# 1_V2.net
KiCad netlist of a schematic drawn in Altium Designer
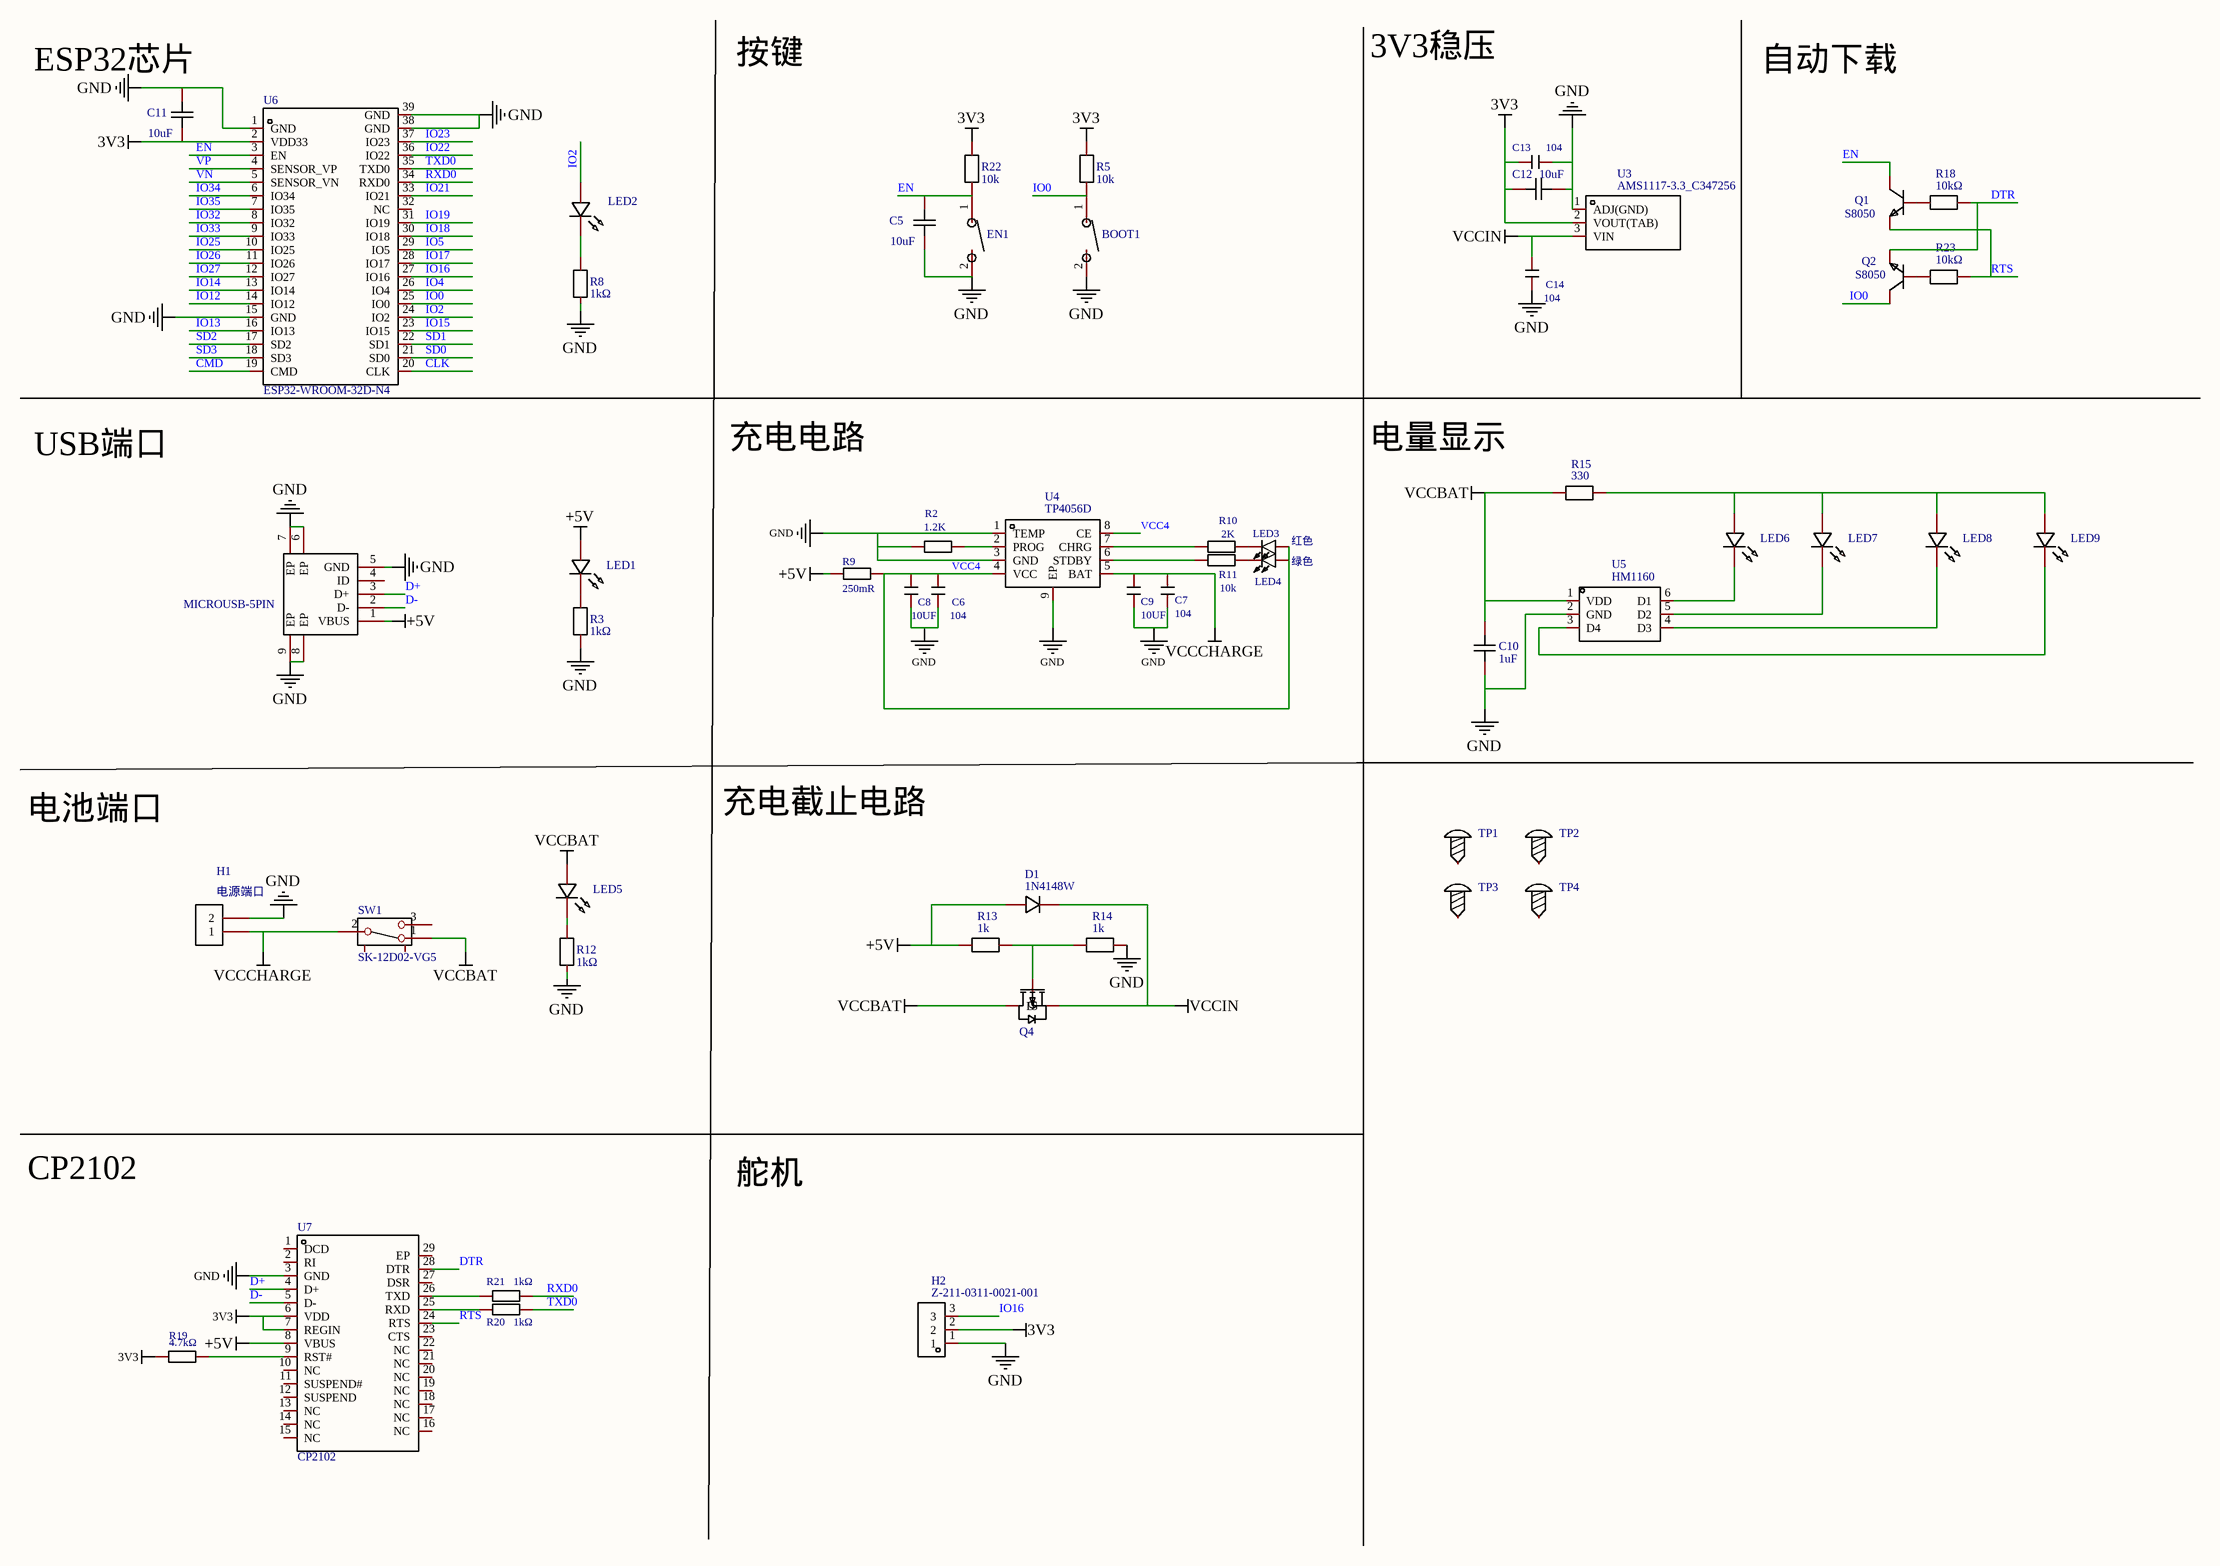
[diagram p0: 1_V2.schdoc]

(export (version "E")
  (design (tool "Eeschema 10.0.6"))
  (components
    (comp (ref "BOOT1")
      (value "TSA343G00-250J2")
      (fields (field (name "MANUFACTURER") "BRIGHT(博瑞泰)"))
      (libsource (lib "altium-import") (part "root_3_TSA343G00-250J2_"))
    )
    (comp (ref "C5")
      (value "10uF")
      (fields (field (name "NAME") "10uF"))
      (libsource (lib "altium-import") (part "root_1_10uF_"))
    )
    (comp (ref "C6")
      (value "104")
      (fields (field (name "NAME") "104") (field (name "版权归属") "源创客"))
      (libsource (lib "altium-import") (part "root_1_104_"))
    )
    (comp (ref "C7")
      (value "104")
      (fields (field (name "NAME") "104") (field (name "版权归属") "源创客"))
      (libsource (lib "altium-import") (part "root_1_104_"))
    )
    (comp (ref "C8")
      (value "10UF")
      (fields (field (name "NAME") "10UF") (field (name "版权归属") "源创客"))
      (libsource (lib "altium-import") (part "root_1_10UF_"))
    )
    (comp (ref "C9")
      (value "10UF")
      (fields (field (name "NAME") "10UF") (field (name "版权归属") "源创客"))
      (libsource (lib "altium-import") (part "root_1_10UF_"))
    )
    (comp (ref "C10")
      (value "1uF")
      (fields (field (name "NAME") "1uF"))
      (libsource (lib "altium-import") (part "root_1_1uF_"))
    )
    (comp (ref "C11")
      (value "10uF")
      (fields (field (name "NAME") "10uF"))
      (libsource (lib "altium-import") (part "root_1_10uF_"))
    )
    (comp (ref "C12")
      (value "10uF")
      (fields (field (name "NAME") "10uF"))
      (libsource (lib "altium-import") (part "root_0_10uF_"))
    )
    (comp (ref "C13")
      (value "104")
      (fields (field (name "NAME") "104") (field (name "版权归属") "源创客"))
      (libsource (lib "altium-import") (part "root_2_104_"))
    )
    (comp (ref "C14")
      (value "104")
      (fields (field (name "NAME") "104") (field (name "版权归属") "源创客"))
      (libsource (lib "altium-import") (part "root_1_104_"))
    )
    (comp (ref "D1")
      (value "1N4148W")
      (fields (field (name "NAME") "1N4148W") (field (name "MANUFACTURER") "Tak Cheong"))
      (libsource (lib "altium-import") (part "root_0_1N4148W_"))
    )
    (comp (ref "EN1")
      (value "TSA343G00-250J2")
      (fields (field (name "MANUFACTURER") "BRIGHT(博瑞泰)"))
      (libsource (lib "altium-import") (part "root_3_TSA343G00-250J2_"))
    )
    (comp (ref "H1")
      (value "电源端口")
      (fields
        (field (name "NAME") "电源端口")
        (field (name "MANUFACTURER") "TE Connectivity(美国泰科)")
        (field (name "MANUFACTURER PART") "3-644456-2")
      )
      (libsource (lib "altium-import") (part "root_2_电源端口_"))
    )
    (comp (ref "H2")
      (value "Z-211-0311-0021-001")
      (fields (field (name "NAME") "Z-211-0311-0021-001") (field (name "MANUFACTURER") "Nextron(正凌)"))
      (libsource (lib "altium-import") (part "root_2_Z-211-0311-0021-001_"))
    )
    (comp (ref "LED1")
      (value "LED-0603_R")
      (fields
        (field (name "MANUFACTURER") "EVERLIGHT(台湾亿光)")
        (field (name "MANUFACTURER PART") "19-217/R6C-AL1M2VY/3T")
      )
      (libsource (lib "altium-import") (part "root_3_LED-0603_R_"))
    )
    (comp (ref "LED2")
      (value "VLMTG1401-GS08")
      (description "照明颜色:-;色温 - CCT（K）:-;主波长/色坐标:-;正向电压（Vf）:-;")
      (fields (field (name "MANUFACTURER") "VISHAY(威世)"))
      (libsource (lib "altium-import") (part "root_3_VLMTG1401-GS08_"))
    )
    (comp (ref "LED3")
      (value "红色")
      (fields (field (name "NAME") "红色") (field (name "版权归属") "源创客"))
      (libsource (lib "altium-import") (part "root_3_红色_"))
    )
    (comp (ref "LED4")
      (value "绿色")
      (fields (field (name "NAME") "绿色") (field (name "版权归属") "源创客"))
      (libsource (lib "altium-import") (part "root_3_绿色_"))
    )
    (comp (ref "LED5")
      (value "LED-0603_R")
      (fields
        (field (name "MANUFACTURER") "EVERLIGHT(台湾亿光)")
        (field (name "MANUFACTURER PART") "19-217/R6C-AL1M2VY/3T")
      )
      (libsource (lib "altium-import") (part "root_3_LED-0603_R_"))
    )
    (comp (ref "LED6")
      (value "LED-0603_R")
      (fields
        (field (name "MANUFACTURER") "EVERLIGHT(台湾亿光)")
        (field (name "MANUFACTURER PART") "19-217/R6C-AL1M2VY/3T")
      )
      (libsource (lib "altium-import") (part "root_3_LED-0603_R_"))
    )
    (comp (ref "LED7")
      (value "LED-0603_R")
      (fields
        (field (name "MANUFACTURER") "EVERLIGHT(台湾亿光)")
        (field (name "MANUFACTURER PART") "19-217/R6C-AL1M2VY/3T")
      )
      (libsource (lib "altium-import") (part "root_3_LED-0603_R_"))
    )
    (comp (ref "LED8")
      (value "LED-0603_R")
      (fields
        (field (name "MANUFACTURER") "EVERLIGHT(台湾亿光)")
        (field (name "MANUFACTURER PART") "19-217/R6C-AL1M2VY/3T")
      )
      (libsource (lib "altium-import") (part "root_3_LED-0603_R_"))
    )
    (comp (ref "LED9")
      (value "LED-0603_R")
      (fields
        (field (name "MANUFACTURER") "EVERLIGHT(台湾亿光)")
        (field (name "MANUFACTURER PART") "19-217/R6C-AL1M2VY/3T")
      )
      (libsource (lib "altium-import") (part "root_3_LED-0603_R_"))
    )
    (comp (ref "NO1")
      (value "MICROUSB-5PIN")
      (fields (field (name "NAME") "MICROUSB-5PIN") (field (name "MANUFACTURER PART") "MicroUSB-5PIN"))
      (libsource (lib "altium-import") (part "root_2_MICROUSB-5PIN_"))
    )
    (comp (ref "Q1")
      (value "S8050")
      (fields (field (name "NAME") "S8050") (field (name "MANUFACTURER") "WPMtek(维攀微)"))
      (libsource (lib "altium-import") (part "root_0_S8050_"))
    )
    (comp (ref "Q2")
      (value "S8050")
      (fields (field (name "NAME") "S8050") (field (name "MANUFACTURER") "WPMtek(维攀微)"))
      (libsource (lib "altium-import") (part "root_2_S8050_"))
    )
    (comp (ref "Q4")
      (value "AO3401A_P")
      (libsource (lib "altium-import") (part "root_3_mirrored_AO3401A_P_"))
    )
    (comp (ref "R2")
      (value "1.2K")
      (fields (field (name "NAME") "1.2K") (field (name "版权归属") "源创客"))
      (libsource (lib "altium-import") (part "root_0_1K_"))
    )
    (comp (ref "R3")
      (value "1kΩ")
      (fields
        (field (name "NAME") "1kΩ")
        (field (name "MANUFACTURER") "PANASONIC(松下)")
        (field (name "MANUFACTURER PART") "ERA3VEB1001V")
        (field (name "TOLERANCE") "±0.1%")
      )
      (libsource (lib "altium-import") (part "root_3_ERA3VEB1001V_"))
    )
    (comp (ref "R5")
      (value "10k")
      (fields (field (name "NAME") "10k"))
      (libsource (lib "altium-import") (part "root_1_10k_"))
    )
    (comp (ref "R8")
      (value "1kΩ")
      (fields
        (field (name "NAME") "1kΩ")
        (field (name "MANUFACTURER") "PANASONIC(松下)")
        (field (name "MANUFACTURER PART") "ERA3VEB1001V")
        (field (name "TOLERANCE") "±0.1%")
      )
      (libsource (lib "altium-import") (part "root_3_ERA3VEB1001V_"))
    )
    (comp (ref "R9")
      (value "250mR")
      (fields (field (name "NAME") "250mR") (field (name "版权归属") "源创客"))
      (libsource (lib "altium-import") (part "root_0_250mR_"))
    )
    (comp (ref "R10")
      (value "2K")
      (fields (field (name "NAME") "2K") (field (name "版权归属") "源创客"))
      (libsource (lib "altium-import") (part "root_0_2K_"))
    )
    (comp (ref "R11")
      (value "10k")
      (fields (field (name "NAME") "10k") (field (name "版权归属") "源创客"))
      (libsource (lib "altium-import") (part "root_0_10k_"))
    )
    (comp (ref "R12")
      (value "1kΩ")
      (fields
        (field (name "NAME") "1kΩ")
        (field (name "MANUFACTURER") "PANASONIC(松下)")
        (field (name "MANUFACTURER PART") "ERA3VEB1001V")
        (field (name "TOLERANCE") "±0.1%")
      )
      (libsource (lib "altium-import") (part "root_3_ERA3VEB1001V_"))
    )
    (comp (ref "R13")
      (value "1k")
      (fields (field (name "NAME") "1k"))
      (libsource (lib "altium-import") (part "root_0_1k_"))
    )
    (comp (ref "R14")
      (value "1k")
      (fields (field (name "NAME") "1k"))
      (libsource (lib "altium-import") (part "root_0_1k_"))
    )
    (comp (ref "R15")
      (value "330")
      (fields (field (name "NAME") "330"))
      (libsource (lib "altium-import") (part "root_0_330_"))
    )
    (comp (ref "R18")
      (value "10kΩ")
      (description "电阻类型:厚膜电阻;阻值:10kΩ;精度:±0.1%;功率:200mW;温度系数:±50ppm/℃;最大工作电压:200V;工作温度范围:-55℃~+155℃;")
      (fields
        (field (name "NAME") "10kΩ")
        (field (name "MANUFACTURER") "PANASONIC(松下)")
        (field (name "MANUFACTURER PART") "ERJPB3B1002V")
      )
      (libsource (lib "altium-import") (part "root_0_ERJPB3B1002V_"))
    )
    (comp (ref "R19")
      (value "4.7kΩ")
      (description "电阻类型:薄膜电阻;阻值:4.7kΩ;精度:±0.1%;功率:125mW;")
      (fields
        (field (name "NAME") "4.7kΩ")
        (field (name "MANUFACTURER") "VISHAY(威世)")
        (field (name "MANUFACTURER PART") "TNPW06034K70BEEA")
        (field (name "版权归属") "源创客")
      )
      (libsource (lib "altium-import") (part "root_0_TNPW06034K70BEEA_"))
    )
    (comp (ref "R20")
      (value "1kΩ")
      (fields
        (field (name "NAME") "1kΩ")
        (field (name "MANUFACTURER") "PANASONIC(松下)")
        (field (name "MANUFACTURER PART") "ERA3VEB1001V")
        (field (name "TOLERANCE") "±0.1%")
        (field (name "版权归属") "源创客")
      )
      (libsource (lib "altium-import") (part "root_0_ERA3VEB1001V_"))
    )
    (comp (ref "R21")
      (value "1kΩ")
      (fields
        (field (name "NAME") "1kΩ")
        (field (name "MANUFACTURER") "PANASONIC(松下)")
        (field (name "MANUFACTURER PART") "ERA3VEB1001V")
        (field (name "TOLERANCE") "±0.1%")
        (field (name "版权归属") "源创客")
      )
      (libsource (lib "altium-import") (part "root_0_ERA3VEB1001V_"))
    )
    (comp (ref "R22")
      (value "10k")
      (fields (field (name "NAME") "10k"))
      (libsource (lib "altium-import") (part "root_1_10k_"))
    )
    (comp (ref "R23")
      (value "10kΩ")
      (description "电阻类型:厚膜电阻;阻值:10kΩ;精度:±0.1%;功率:200mW;温度系数:±50ppm/℃;最大工作电压:200V;工作温度范围:-55℃~+155℃;")
      (fields
        (field (name "NAME") "10kΩ")
        (field (name "MANUFACTURER") "PANASONIC(松下)")
        (field (name "MANUFACTURER PART") "ERJPB3B1002V")
      )
      (libsource (lib "altium-import") (part "root_0_ERJPB3B1002V_"))
    )
    (comp (ref "SW1")
      (value "SK-12D02-VG5")
      (fields (field (name "NAME") "SK-12D02-VG5") (field (name "MANUFACTURER") "韩国韩荣"))
      (libsource (lib "altium-import") (part "root_0_SK-12D02-VG5_C136722_"))
    )
    (comp (ref "TP1") (value "M2螺丝") (libsource (lib "altium-import") (part "root_0_M2螺丝_")))
    (comp (ref "TP2") (value "M2螺丝") (libsource (lib "altium-import") (part "root_0_M2螺丝_")))
    (comp (ref "TP3") (value "M2螺丝") (libsource (lib "altium-import") (part "root_0_M2螺丝_")))
    (comp (ref "TP4") (value "M2螺丝") (libsource (lib "altium-import") (part "root_0_M2螺丝_")))
    (comp (ref "U3")
      (value "AMS1117-3.3_C347256")
      (fields
        (field (name "NAME") "AMS1117-3.3_C347256")
        (field (name "MANUFACTURER") "Youtai Semiconductor Co., Ltd.")
        (field (name "MANUFACTURER PART") "AMS1117-3.3")
      )
      (libsource (lib "altium-import") (part "root_0_AMS1117-3.3_C347256_"))
    )
    (comp (ref "U4")
      (value "TP4056D")
      (fields (field (name "NAME") "TP4056D") (field (name "MANUFACTURER") "拓微集成"))
      (libsource (lib "altium-import") (part "root_0_TP4056D_"))
    )
    (comp (ref "U5")
      (value "HM1160")
      (fields
        (field (name "NAME") "HM1160")
        (field (name "MANUFACTURER") "Shenzhen Chip Hope Micro-Electronics")
        (field (name "MANUFACTURER PART") "LP3772-1")
      )
      (libsource (lib "altium-import") (part "root_0_HM1160_"))
    )
    (comp (ref "U6")
      (value "ESP32-WROOM-32D-N4")
      (description "ESP32-WROOM-32D 集成 ESP32-D0WD，功能强大，用途广泛，可以用于低功耗传感器网络和要求极高的任务，例如语音编码、音频流和 MP3 解码等。")
      (fields (field (name "NAME") "ESP32-WROOM-32D-N4") (field (name "MANUFACTURER") "ESPRESSIF(乐鑫)"))
      (libsource (lib "altium-import") (part "root_0_ESP32-WROOM-32D-N4_C473012_"))
    )
    (comp (ref "U7")
      (value "CP2102")
      (fields (field (name "NAME") "CP2102"))
      (libsource (lib "altium-import") (part "root_0_CP2102_"))
    )
  )
  (nets
    (net (code "1") (name "+5V") (class "Default")
      (node (ref "D1") (pin "2") (pinfunction "2_2") (pintype "passive"))
      (node (ref "LED1") (pin "1") (pinfunction "1_1") (pintype "passive"))
      (node (ref "NO1") (pin "1") (pinfunction "VBUS_1") (pintype "passive"))
      (node (ref "R13") (pin "1") (pinfunction "1_1") (pintype "passive"))
      (node (ref "R9") (pin "1") (pinfunction "1_1") (pintype "passive"))
      (node (ref "U7") (pin "8") (pinfunction "VBUS_8") (pintype "passive"))
    )
    (net (code "2") (name "/CLK") (class "Default")
      (node (ref "U6") (pin "20") (pinfunction "CLK_20") (pintype "passive"))
    )
    (net (code "3") (name "/CMD") (class "Default")
      (node (ref "U6") (pin "19") (pinfunction "CMD_19") (pintype "passive"))
    )
    (net (code "4") (name "/D+") (class "Default")
      (node (ref "NO1") (pin "3") (pinfunction "D+_3") (pintype "passive"))
      (node (ref "U7") (pin "4") (pinfunction "D+_4") (pintype "passive"))
    )
    (net (code "5") (name "/D-") (class "Default")
      (node (ref "NO1") (pin "2") (pinfunction "D-_2") (pintype "passive"))
      (node (ref "U7") (pin "5") (pinfunction "D-_5") (pintype "passive"))
    )
    (net (code "6") (name "/DTR") (class "Default")
      (node (ref "Q2") (pin "2") (pinfunction "E_2") (pintype "passive"))
      (node (ref "R18") (pin "2") (pinfunction "2_2") (pintype "passive"))
      (node (ref "U7") (pin "28") (pinfunction "DTR_28") (pintype "passive"))
    )
    (net (code "7") (name "/EN") (class "Default")
      (node (ref "C5") (pin "2") (pinfunction "2_2") (pintype "passive"))
      (node (ref "EN1") (pin "1") (pinfunction "1_1") (pintype "passive"))
      (node (ref "Q1") (pin "3") (pinfunction "C_3") (pintype "passive"))
      (node (ref "R22") (pin "1") (pinfunction "1_1") (pintype "passive"))
      (node (ref "U6") (pin "3") (pinfunction "EN_3") (pintype "passive"))
    )
    (net (code "8") (name "/IO0") (class "Default")
      (node (ref "BOOT1") (pin "1") (pinfunction "1_1") (pintype "passive"))
      (node (ref "Q2") (pin "3") (pinfunction "C_3") (pintype "passive"))
      (node (ref "R5") (pin "1") (pinfunction "1_1") (pintype "passive"))
      (node (ref "U6") (pin "25") (pinfunction "IO0_25") (pintype "passive"))
    )
    (net (code "9") (name "/IO2") (class "Default")
      (node (ref "LED2") (pin "1") (pinfunction "1_1") (pintype "passive"))
      (node (ref "U6") (pin "24") (pinfunction "IO2_24") (pintype "passive"))
    )
    (net (code "10") (name "/IO4") (class "Default")
      (node (ref "U6") (pin "26") (pinfunction "IO4_26") (pintype "passive"))
    )
    (net (code "11") (name "/IO5") (class "Default")
      (node (ref "U6") (pin "29") (pinfunction "IO5_29") (pintype "passive"))
    )
    (net (code "12") (name "/IO12") (class "Default")
      (node (ref "U6") (pin "14") (pinfunction "IO12_14") (pintype "passive"))
    )
    (net (code "13") (name "/IO13") (class "Default")
      (node (ref "U6") (pin "16") (pinfunction "IO13_16") (pintype "passive"))
    )
    (net (code "14") (name "/IO14") (class "Default")
      (node (ref "U6") (pin "13") (pinfunction "IO14_13") (pintype "passive"))
    )
    (net (code "15") (name "/IO15") (class "Default")
      (node (ref "U6") (pin "23") (pinfunction "IO15_23") (pintype "passive"))
    )
    (net (code "16") (name "/IO16") (class "Default")
      (node (ref "H2") (pin "3") (pinfunction "3_3") (pintype "passive"))
      (node (ref "U6") (pin "27") (pinfunction "IO16_27") (pintype "passive"))
    )
    (net (code "17") (name "/IO17") (class "Default")
      (node (ref "U6") (pin "28") (pinfunction "IO17_28") (pintype "passive"))
    )
    (net (code "18") (name "/IO18") (class "Default")
      (node (ref "U6") (pin "30") (pinfunction "IO18_30") (pintype "passive"))
    )
    (net (code "19") (name "/IO19") (class "Default")
      (node (ref "U6") (pin "31") (pinfunction "IO19_31") (pintype "passive"))
    )
    (net (code "20") (name "/IO21") (class "Default")
      (node (ref "U6") (pin "33") (pinfunction "IO21_33") (pintype "passive"))
    )
    (net (code "21") (name "/IO22") (class "Default")
      (node (ref "U6") (pin "36") (pinfunction "IO22_36") (pintype "passive"))
    )
    (net (code "22") (name "/IO23") (class "Default")
      (node (ref "U6") (pin "37") (pinfunction "IO23_37") (pintype "passive"))
    )
    (net (code "23") (name "/IO25") (class "Default")
      (node (ref "U6") (pin "10") (pinfunction "IO25_10") (pintype "passive"))
    )
    (net (code "24") (name "/IO26") (class "Default")
      (node (ref "U6") (pin "11") (pinfunction "IO26_11") (pintype "passive"))
    )
    (net (code "25") (name "/IO27") (class "Default")
      (node (ref "U6") (pin "12") (pinfunction "IO27_12") (pintype "passive"))
    )
    (net (code "26") (name "/IO32") (class "Default")
      (node (ref "U6") (pin "8") (pinfunction "IO32_8") (pintype "passive"))
    )
    (net (code "27") (name "/IO33") (class "Default")
      (node (ref "U6") (pin "9") (pinfunction "IO33_9") (pintype "passive"))
    )
    (net (code "28") (name "/IO34") (class "Default")
      (node (ref "U6") (pin "6") (pinfunction "IO34_6") (pintype "passive"))
    )
    (net (code "29") (name "/IO35") (class "Default")
      (node (ref "U6") (pin "7") (pinfunction "IO35_7") (pintype "passive"))
    )
    (net (code "30") (name "/RTS") (class "Default")
      (node (ref "Q1") (pin "2") (pinfunction "E_2") (pintype "passive"))
      (node (ref "R23") (pin "2") (pinfunction "2_2") (pintype "passive"))
      (node (ref "U7") (pin "24") (pinfunction "RTS_24") (pintype "passive"))
    )
    (net (code "31") (name "/RXD0") (class "Default")
      (node (ref "R21") (pin "2") (pinfunction "2_2") (pintype "passive"))
      (node (ref "U6") (pin "34") (pinfunction "RXD0_34") (pintype "passive"))
    )
    (net (code "32") (name "/SD0") (class "Default")
      (node (ref "U6") (pin "21") (pinfunction "SD0_21") (pintype "passive"))
    )
    (net (code "33") (name "/SD1") (class "Default")
      (node (ref "U6") (pin "22") (pinfunction "SD1_22") (pintype "passive"))
    )
    (net (code "34") (name "/SD2") (class "Default")
      (node (ref "U6") (pin "17") (pinfunction "SD2_17") (pintype "passive"))
    )
    (net (code "35") (name "/SD3") (class "Default")
      (node (ref "U6") (pin "18") (pinfunction "SD3_18") (pintype "passive"))
    )
    (net (code "36") (name "/TXD0") (class "Default")
      (node (ref "R20") (pin "2") (pinfunction "2_2") (pintype "passive"))
      (node (ref "U6") (pin "35") (pinfunction "TXD0_35") (pintype "passive"))
    )
    (net (code "37") (name "/VCC4") (class "Default")
      (node (ref "C6") (pin "2") (pinfunction "2_2") (pintype "passive"))
      (node (ref "C8") (pin "2") (pinfunction "2_2") (pintype "passive"))
      (node (ref "LED3") (pin "1") (pinfunction "A_1") (pintype "passive"))
      (node (ref "LED4") (pin "1") (pinfunction "A_1") (pintype "passive"))
      (node (ref "R9") (pin "2") (pinfunction "2_2") (pintype "passive"))
      (node (ref "U4") (pin "4") (pinfunction "VCC_4") (pintype "passive"))
      (node (ref "U4") (pin "8") (pinfunction "CE_8") (pintype "passive"))
    )
    (net (code "38") (name "/VN") (class "Default")
      (node (ref "U6") (pin "5") (pinfunction "SENSOR_VN_5") (pintype "passive"))
    )
    (net (code "39") (name "/VP") (class "Default")
      (node (ref "U6") (pin "4") (pinfunction "SENSOR_VP_4") (pintype "passive"))
    )
    (net (code "40") (name "3V3") (class "Default")
      (node (ref "C11") (pin "1") (pinfunction "1_1") (pintype "passive"))
      (node (ref "C12") (pin "1") (pinfunction "1_1") (pintype "passive"))
      (node (ref "C13") (pin "2") (pinfunction "2_2") (pintype "passive"))
      (node (ref "H2") (pin "2") (pinfunction "2_2") (pintype "passive"))
      (node (ref "R19") (pin "1") (pinfunction "1_1") (pintype "passive"))
      (node (ref "R22") (pin "2") (pinfunction "2_2") (pintype "passive"))
      (node (ref "R5") (pin "2") (pinfunction "2_2") (pintype "passive"))
      (node (ref "U3") (pin "2") (pinfunction "VOUT(TAB)_2") (pintype "passive"))
      (node (ref "U6") (pin "2") (pinfunction "VDD33_2") (pintype "passive"))
      (node (ref "U7") (pin "6") (pinfunction "VDD_6") (pintype "passive"))
      (node (ref "U7") (pin "7") (pinfunction "REGIN_7") (pintype "passive"))
    )
    (net (code "41") (name "GND") (class "Default")
      (node (ref "BOOT1") (pin "2") (pinfunction "2_2") (pintype "passive"))
      (node (ref "C10") (pin "1") (pinfunction "1_1") (pintype "passive"))
      (node (ref "C11") (pin "2") (pinfunction "2_2") (pintype "passive"))
      (node (ref "C12") (pin "2") (pinfunction "2_2") (pintype "passive"))
      (node (ref "C13") (pin "1") (pinfunction "1_1") (pintype "passive"))
      (node (ref "C14") (pin "1") (pinfunction "1_1") (pintype "passive"))
      (node (ref "C5") (pin "1") (pinfunction "1_1") (pintype "passive"))
      (node (ref "C6") (pin "1") (pinfunction "1_1") (pintype "passive"))
      (node (ref "C7") (pin "1") (pinfunction "1_1") (pintype "passive"))
      (node (ref "C8") (pin "1") (pinfunction "1_1") (pintype "passive"))
      (node (ref "C9") (pin "1") (pinfunction "1_1") (pintype "passive"))
      (node (ref "EN1") (pin "2") (pinfunction "2_2") (pintype "passive"))
      (node (ref "H1") (pin "2") (pinfunction "2_2") (pintype "passive"))
      (node (ref "H2") (pin "1") (pinfunction "1_1") (pintype "passive"))
      (node (ref "NO1") (pin "5") (pinfunction "GND_5") (pintype "passive"))
      (node (ref "NO1") (pin "6") (pinfunction "EP_6") (pintype "passive"))
      (node (ref "NO1") (pin "7") (pinfunction "EP_7") (pintype "passive"))
      (node (ref "NO1") (pin "8") (pinfunction "EP_8") (pintype "passive"))
      (node (ref "NO1") (pin "9") (pinfunction "EP_9") (pintype "passive"))
      (node (ref "R12") (pin "2") (pinfunction "2_2") (pintype "passive"))
      (node (ref "R14") (pin "2") (pinfunction "2_2") (pintype "passive"))
      (node (ref "R2") (pin "1") (pinfunction "1_1") (pintype "passive"))
      (node (ref "R3") (pin "2") (pinfunction "2_2") (pintype "passive"))
      (node (ref "R8") (pin "2") (pinfunction "2_2") (pintype "passive"))
      (node (ref "U3") (pin "1") (pinfunction "ADJ(GND)_1") (pintype "passive"))
      (node (ref "U4") (pin "1") (pinfunction "TEMP_1") (pintype "passive"))
      (node (ref "U4") (pin "3") (pinfunction "GND_3") (pintype "passive"))
      (node (ref "U4") (pin "9") (pinfunction "EP_9") (pintype "passive"))
      (node (ref "U5") (pin "2") (pinfunction "GND_2") (pintype "passive"))
      (node (ref "U6") (pin "1") (pinfunction "GND_1") (pintype "passive"))
      (node (ref "U6") (pin "15") (pinfunction "GND_15") (pintype "passive"))
      (node (ref "U6") (pin "38") (pinfunction "GND_38") (pintype "passive"))
      (node (ref "U6") (pin "39") (pinfunction "GND_39") (pintype "passive"))
      (node (ref "U7") (pin "3") (pinfunction "GND_3") (pintype "passive"))
    )
    (net (code "42") (name "Net-(LED1-Pad2)") (class "Default")
      (node (ref "LED1") (pin "2") (pinfunction "2_2") (pintype "passive"))
      (node (ref "R3") (pin "1") (pinfunction "1_1") (pintype "passive"))
    )
    (net (code "43") (name "Net-(LED2-Pad2)") (class "Default")
      (node (ref "LED2") (pin "2") (pinfunction "2_2") (pintype "passive"))
      (node (ref "R8") (pin "1") (pinfunction "1_1") (pintype "passive"))
    )
    (net (code "44") (name "Net-(LED3-K)") (class "Default")
      (node (ref "LED3") (pin "2") (pinfunction "K_2") (pintype "passive"))
      (node (ref "R10") (pin "2") (pinfunction "2_2") (pintype "passive"))
    )
    (net (code "45") (name "Net-(LED4-K)") (class "Default")
      (node (ref "LED4") (pin "2") (pinfunction "K_2") (pintype "passive"))
      (node (ref "R11") (pin "2") (pinfunction "2_2") (pintype "passive"))
    )
    (net (code "46") (name "Net-(LED5-Pad2)") (class "Default")
      (node (ref "LED5") (pin "2") (pinfunction "2_2") (pintype "passive"))
      (node (ref "R12") (pin "1") (pinfunction "1_1") (pintype "passive"))
    )
    (net (code "47") (name "Net-(LED6-Pad1)") (class "Default")
      (node (ref "LED6") (pin "1") (pinfunction "1_1") (pintype "passive"))
      (node (ref "LED7") (pin "1") (pinfunction "1_1") (pintype "passive"))
      (node (ref "LED8") (pin "1") (pinfunction "1_1") (pintype "passive"))
      (node (ref "LED9") (pin "1") (pinfunction "1_1") (pintype "passive"))
      (node (ref "R15") (pin "2") (pinfunction "2_2") (pintype "passive"))
    )
    (net (code "48") (name "Net-(Q1-B)") (class "Default")
      (node (ref "Q1") (pin "1") (pinfunction "B_1") (pintype "passive"))
      (node (ref "R18") (pin "1") (pinfunction "1_1") (pintype "passive"))
    )
    (net (code "49") (name "Net-(Q2-B)") (class "Default")
      (node (ref "Q2") (pin "1") (pinfunction "B_1") (pintype "passive"))
      (node (ref "R23") (pin "1") (pinfunction "1_1") (pintype "passive"))
    )
    (net (code "50") (name "Net-(Q4-G)") (class "Default")
      (node (ref "Q4") (pin "1") (pinfunction "G_1") (pintype "passive"))
      (node (ref "R13") (pin "2") (pinfunction "2_2") (pintype "passive"))
      (node (ref "R14") (pin "1") (pinfunction "1_1") (pintype "passive"))
    )
    (net (code "51") (name "Net-(U4-CHRG)") (class "Default")
      (node (ref "R10") (pin "1") (pinfunction "1_1") (pintype "passive"))
      (node (ref "U4") (pin "7") (pinfunction "CHRG_7") (pintype "passive"))
    )
    (net (code "52") (name "Net-(U4-PROG)") (class "Default")
      (node (ref "R2") (pin "2") (pinfunction "2_2") (pintype "passive"))
      (node (ref "U4") (pin "2") (pinfunction "PROG_2") (pintype "passive"))
    )
    (net (code "53") (name "Net-(U4-STDBY)") (class "Default")
      (node (ref "R11") (pin "1") (pinfunction "1_1") (pintype "passive"))
      (node (ref "U4") (pin "6") (pinfunction "STDBY_6") (pintype "passive"))
    )
    (net (code "54") (name "Net-(U5-D1)") (class "Default")
      (node (ref "LED6") (pin "2") (pinfunction "2_2") (pintype "passive"))
      (node (ref "U5") (pin "6") (pinfunction "D1_6") (pintype "passive"))
    )
    (net (code "55") (name "Net-(U5-D2)") (class "Default")
      (node (ref "LED7") (pin "2") (pinfunction "2_2") (pintype "passive"))
      (node (ref "U5") (pin "5") (pinfunction "D2_5") (pintype "passive"))
    )
    (net (code "56") (name "Net-(U5-D3)") (class "Default")
      (node (ref "LED8") (pin "2") (pinfunction "2_2") (pintype "passive"))
      (node (ref "U5") (pin "4") (pinfunction "D3_4") (pintype "passive"))
    )
    (net (code "57") (name "Net-(U5-D4)") (class "Default")
      (node (ref "LED9") (pin "2") (pinfunction "2_2") (pintype "passive"))
      (node (ref "U5") (pin "3") (pinfunction "D4_3") (pintype "passive"))
    )
    (net (code "58") (name "Net-(U7-RST#)") (class "Default")
      (node (ref "R19") (pin "2") (pinfunction "2_2") (pintype "passive"))
      (node (ref "U7") (pin "9") (pinfunction "RST#_9") (pintype "passive"))
    )
    (net (code "59") (name "Net-(U7-RXD)") (class "Default")
      (node (ref "R20") (pin "1") (pinfunction "1_1") (pintype "passive"))
      (node (ref "U7") (pin "25") (pinfunction "RXD_25") (pintype "passive"))
    )
    (net (code "60") (name "Net-(U7-TXD)") (class "Default")
      (node (ref "R21") (pin "1") (pinfunction "1_1") (pintype "passive"))
      (node (ref "U7") (pin "26") (pinfunction "TXD_26") (pintype "passive"))
    )
    (net (code "61") (name "VCCBAT") (class "Default")
      (node (ref "C10") (pin "2") (pinfunction "2_2") (pintype "passive"))
      (node (ref "LED5") (pin "1") (pinfunction "1_1") (pintype "passive"))
      (node (ref "Q4") (pin "3") (pinfunction "D_3") (pintype "passive"))
      (node (ref "R15") (pin "1") (pinfunction "1_1") (pintype "passive"))
      (node (ref "SW1") (pin "1") (pinfunction "1_1") (pintype "passive"))
      (node (ref "U5") (pin "1") (pinfunction "VDD_1") (pintype "passive"))
    )
    (net (code "62") (name "VCCCHARGE") (class "Default")
      (node (ref "C7") (pin "2") (pinfunction "2_2") (pintype "passive"))
      (node (ref "C9") (pin "2") (pinfunction "2_2") (pintype "passive"))
      (node (ref "H1") (pin "1") (pinfunction "1_1") (pintype "passive"))
      (node (ref "SW1") (pin "2") (pinfunction "2_2") (pintype "passive"))
      (node (ref "U4") (pin "5") (pinfunction "BAT_5") (pintype "passive"))
    )
    (net (code "63") (name "VCCIN") (class "Default")
      (node (ref "C14") (pin "2") (pinfunction "2_2") (pintype "passive"))
      (node (ref "D1") (pin "1") (pinfunction "1_1") (pintype "passive"))
      (node (ref "Q4") (pin "2") (pinfunction "S_2") (pintype "passive"))
      (node (ref "U3") (pin "3") (pinfunction "VIN_3") (pintype "passive"))
    )
    (net (code "64") (name "unconnected-(NO1-ID-Pad4)") (class "Default")
      (node (ref "NO1") (pin "4") (pinfunction "ID_4") (pintype "passive"))
    )
    (net (code "65") (name "unconnected-(SW1-Pad3)") (class "Default")
      (node (ref "SW1") (pin "3") (pinfunction "3_3") (pintype "passive"))
    )
    (net (code "66") (name "unconnected-(SW1-Pad4)") (class "Default")
      (node (ref "SW1") (pin "4") (pinfunction "4_4") (pintype "passive"))
    )
    (net (code "67") (name "unconnected-(SW1-Pad5)") (class "Default")
      (node (ref "SW1") (pin "5") (pinfunction "5_5") (pintype "passive"))
    )
    (net (code "68") (name "unconnected-(TP1-Pad1)") (class "Default")
      (node (ref "TP1") (pin "1") (pinfunction "1_1") (pintype "passive"))
    )
    (net (code "69") (name "unconnected-(TP2-Pad1)") (class "Default")
      (node (ref "TP2") (pin "1") (pinfunction "1_1") (pintype "passive"))
    )
    (net (code "70") (name "unconnected-(TP3-Pad1)") (class "Default")
      (node (ref "TP3") (pin "1") (pinfunction "1_1") (pintype "passive"))
    )
    (net (code "71") (name "unconnected-(TP4-Pad1)") (class "Default")
      (node (ref "TP4") (pin "1") (pinfunction "1_1") (pintype "passive"))
    )
    (net (code "72") (name "unconnected-(U6-NC-Pad32)") (class "Default")
      (node (ref "U6") (pin "32") (pinfunction "NC_32") (pintype "passive"))
    )
    (net (code "73") (name "unconnected-(U7-CTS-Pad23)") (class "Default")
      (node (ref "U7") (pin "23") (pinfunction "CTS_23") (pintype "passive"))
    )
    (net (code "74") (name "unconnected-(U7-DCD-Pad1)") (class "Default")
      (node (ref "U7") (pin "1") (pinfunction "DCD_1") (pintype "passive"))
    )
    (net (code "75") (name "unconnected-(U7-DSR-Pad27)") (class "Default")
      (node (ref "U7") (pin "27") (pinfunction "DSR_27") (pintype "passive"))
    )
    (net (code "76") (name "unconnected-(U7-EP-Pad29)") (class "Default")
      (node (ref "U7") (pin "29") (pinfunction "EP_29") (pintype "passive"))
    )
    (net (code "77") (name "unconnected-(U7-NC-Pad10)") (class "Default")
      (node (ref "U7") (pin "10") (pinfunction "NC_10") (pintype "passive"))
    )
    (net (code "78") (name "unconnected-(U7-NC-Pad13)") (class "Default")
      (node (ref "U7") (pin "13") (pinfunction "NC_13") (pintype "passive"))
    )
    (net (code "79") (name "unconnected-(U7-NC-Pad14)") (class "Default")
      (node (ref "U7") (pin "14") (pinfunction "NC_14") (pintype "passive"))
    )
    (net (code "80") (name "unconnected-(U7-NC-Pad15)") (class "Default")
      (node (ref "U7") (pin "15") (pinfunction "NC_15") (pintype "passive"))
    )
    (net (code "81") (name "unconnected-(U7-NC-Pad16)") (class "Default")
      (node (ref "U7") (pin "16") (pinfunction "NC_16") (pintype "passive"))
    )
    (net (code "82") (name "unconnected-(U7-NC-Pad17)") (class "Default")
      (node (ref "U7") (pin "17") (pinfunction "NC_17") (pintype "passive"))
    )
    (net (code "83") (name "unconnected-(U7-NC-Pad18)") (class "Default")
      (node (ref "U7") (pin "18") (pinfunction "NC_18") (pintype "passive"))
    )
    (net (code "84") (name "unconnected-(U7-NC-Pad19)") (class "Default")
      (node (ref "U7") (pin "19") (pinfunction "NC_19") (pintype "passive"))
    )
    (net (code "85") (name "unconnected-(U7-NC-Pad20)") (class "Default")
      (node (ref "U7") (pin "20") (pinfunction "NC_20") (pintype "passive"))
    )
    (net (code "86") (name "unconnected-(U7-NC-Pad21)") (class "Default")
      (node (ref "U7") (pin "21") (pinfunction "NC_21") (pintype "passive"))
    )
    (net (code "87") (name "unconnected-(U7-NC-Pad22)") (class "Default")
      (node (ref "U7") (pin "22") (pinfunction "NC_22") (pintype "passive"))
    )
    (net (code "88") (name "unconnected-(U7-RI-Pad2)") (class "Default")
      (node (ref "U7") (pin "2") (pinfunction "RI_2") (pintype "passive"))
    )
    (net (code "89") (name "unconnected-(U7-SUSPEND#-Pad11)") (class "Default")
      (node (ref "U7") (pin "11") (pinfunction "SUSPEND#_11") (pintype "passive"))
    )
    (net (code "90") (name "unconnected-(U7-SUSPEND-Pad12)") (class "Default")
      (node (ref "U7") (pin "12") (pinfunction "SUSPEND_12") (pintype "passive"))
    )
  )
)
